# rectifier.net
KiCad netlist of a schematic drawn in EAGLE
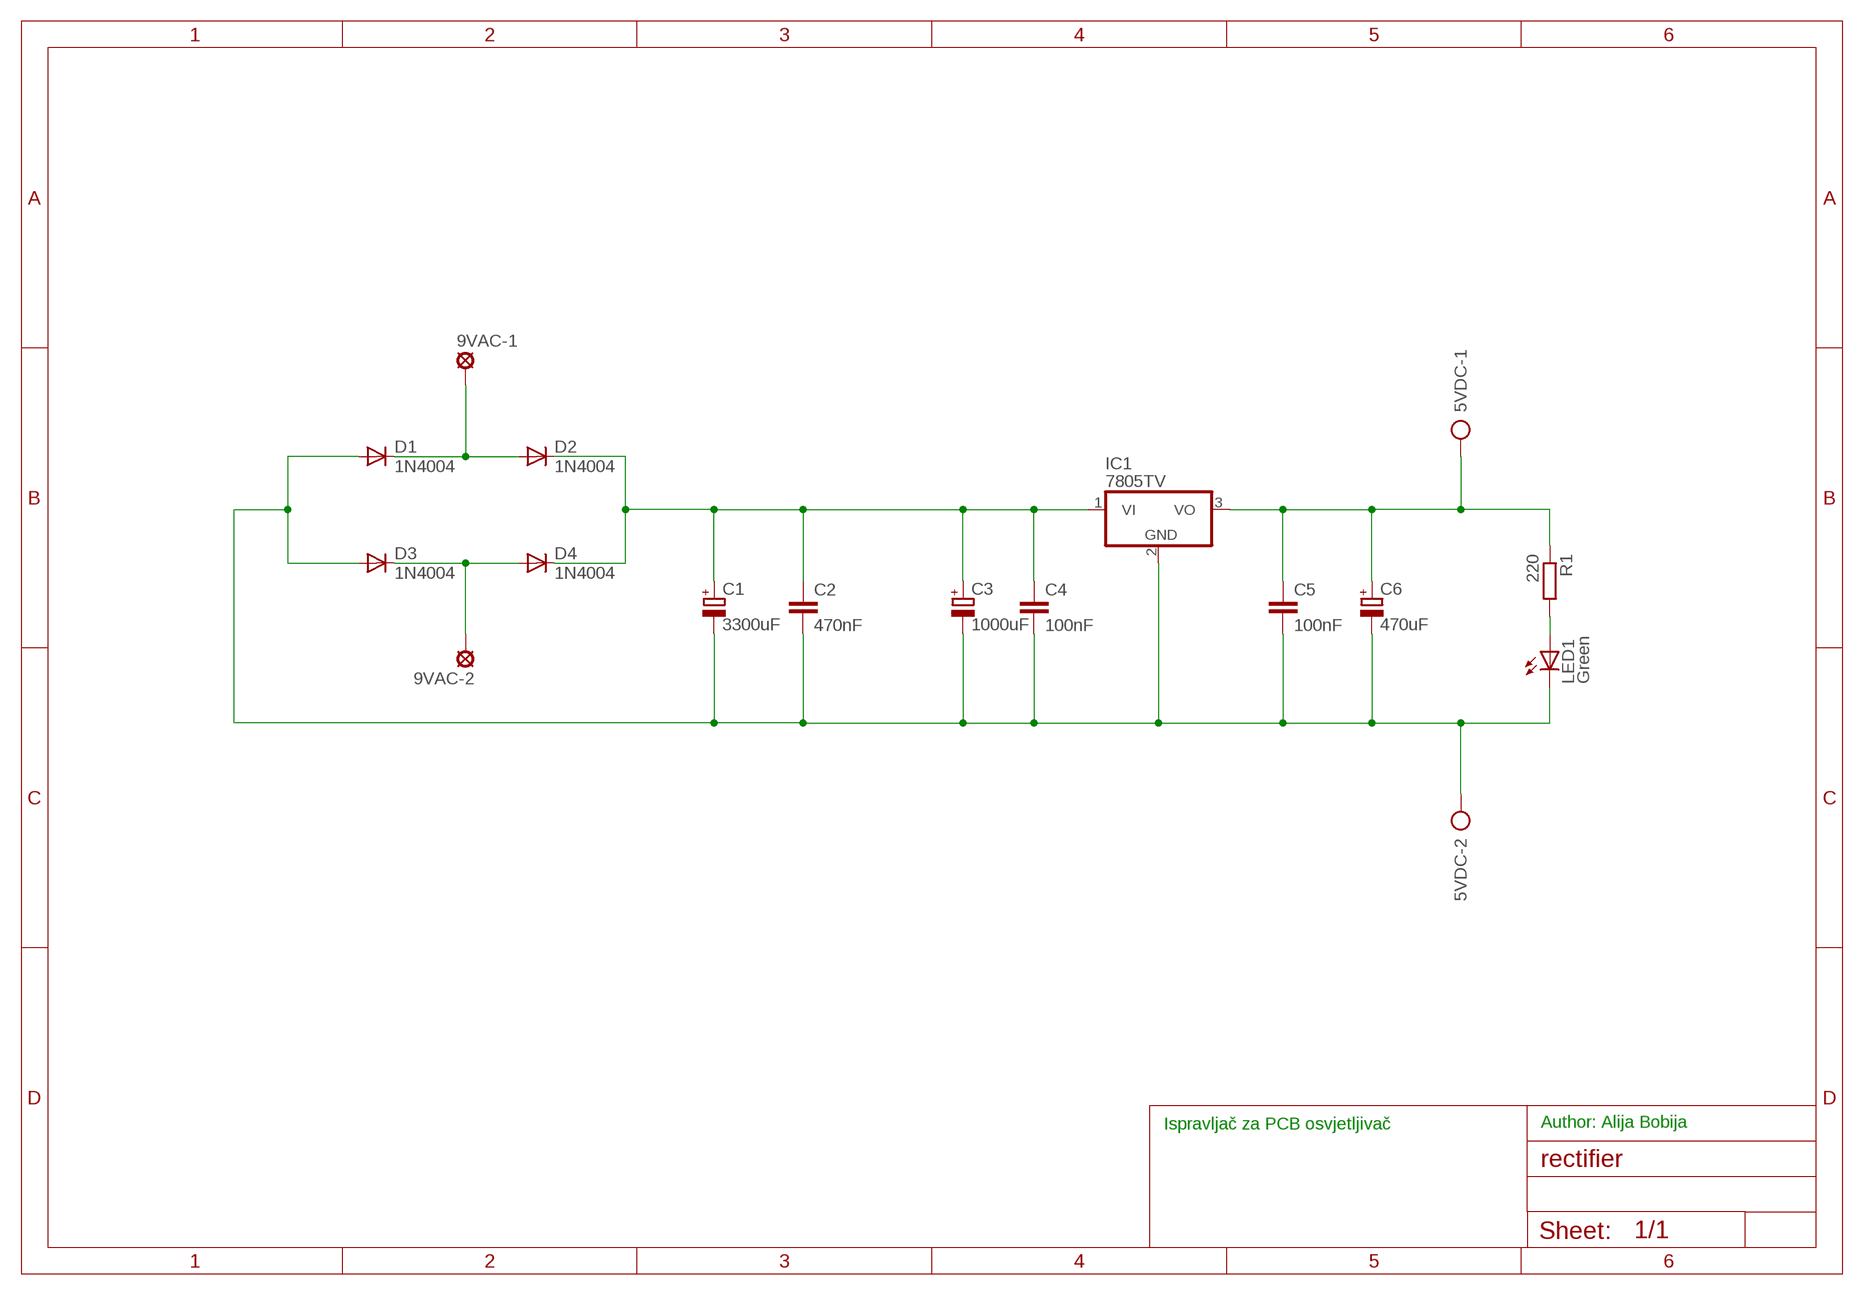
[diagram p0: schematic, sheet 1]

(export (version "E")
  (design (tool "Eeschema 10.0.6"))
  (components
    (comp (ref "5VDC")
      (value "AK500/2")
      (footprint "eagle-import:AK500_2")
      (libsource (lib "eagle-import") (part "AK500/2"))
    )
    (comp (ref "9VAC-1")
      (value "LSP10")
      (footprint "eagle-import:LSP10")
      (libsource (lib "eagle-import") (part "LSP10"))
    )
    (comp (ref "9VAC-2")
      (value "LSP10")
      (footprint "eagle-import:LSP10")
      (libsource (lib "eagle-import") (part "LSP10"))
    )
    (comp (ref "C1")
      (value "3300uF")
      (footprint "eagle-import:E5-13")
      (libsource (lib "eagle-import") (part "resistor_CPOL-EUE5-13"))
    )
    (comp (ref "C2")
      (value "470nF")
      (footprint "eagle-import:C050-024X044")
      (libsource (lib "eagle-import") (part "resistor_C-EU050-024X044"))
    )
    (comp (ref "C3")
      (value "1000uF")
      (footprint "eagle-import:E3,5-10")
      (libsource (lib "eagle-import") (part "CPOL-EUE3.5-10"))
    )
    (comp (ref "C4")
      (value "100nF")
      (footprint "eagle-import:C025-024X044")
      (libsource (lib "eagle-import") (part "C-EU025-024X044"))
    )
    (comp (ref "C5")
      (value "100nF")
      (footprint "eagle-import:C025-024X044")
      (libsource (lib "eagle-import") (part "C-EU025-024X044"))
    )
    (comp (ref "C6")
      (value "470uF")
      (footprint "eagle-import:E3,5-8")
      (libsource (lib "eagle-import") (part "CPOL-EUE3.5-8"))
    )
    (comp (ref "D1")
      (value "1N4004")
      (footprint "eagle-import:DO41-10")
      (libsource (lib "eagle-import") (part "1N4004"))
    )
    (comp (ref "D2")
      (value "1N4004")
      (footprint "eagle-import:DO41-10")
      (libsource (lib "eagle-import") (part "1N4004"))
    )
    (comp (ref "D3")
      (value "1N4004")
      (footprint "eagle-import:DO41-10")
      (libsource (lib "eagle-import") (part "1N4004"))
    )
    (comp (ref "D4")
      (value "1N4004")
      (footprint "eagle-import:DO41-10")
      (libsource (lib "eagle-import") (part "1N4004"))
    )
    (comp (ref "IC1")
      (value "7805TV")
      (footprint "eagle-import:TO220V")
      (libsource (lib "eagle-import") (part "78TV05"))
    )
    (comp (ref "LED1")
      (value "Green")
      (footprint "eagle-import:LED3MM")
      (libsource (lib "eagle-import") (part "LED3MM"))
    )
    (comp (ref "R1")
      (value "220")
      (footprint "eagle-import:M0805")
      (libsource (lib "eagle-import") (part "R-EU_M0805"))
    )
  )
  (nets
    (net (code "1") (name "Net-(5VDCA-KL)") (class "Default")
      (node (ref "5VDC") (pin "1") (pinfunction "KL_1") (pintype "passive"))
      (node (ref "C5") (pin "1") (pinfunction "1_1") (pintype "passive"))
      (node (ref "C6") (pin "+") (pinfunction "+_+") (pintype "passive"))
      (node (ref "IC1") (pin "3") (pinfunction "VO_3") (pintype "passive"))
      (node (ref "R1") (pin "1") (pinfunction "1_1") (pintype "passive"))
    )
    (net (code "2") (name "Net-(5VDCB-KL)") (class "Default")
      (node (ref "5VDC") (pin "2") (pinfunction "KL_2") (pintype "passive"))
      (node (ref "C1") (pin "-") (pinfunction "-_-") (pintype "passive"))
      (node (ref "C2") (pin "2") (pinfunction "2_2") (pintype "passive"))
      (node (ref "C3") (pin "-") (pinfunction "-_-") (pintype "passive"))
      (node (ref "C4") (pin "2") (pinfunction "2_2") (pintype "passive"))
      (node (ref "C5") (pin "2") (pinfunction "2_2") (pintype "passive"))
      (node (ref "C6") (pin "-") (pinfunction "-_-") (pintype "passive"))
      (node (ref "D1") (pin "A") (pinfunction "A_A") (pintype "passive"))
      (node (ref "D3") (pin "A") (pinfunction "A_A") (pintype "passive"))
      (node (ref "IC1") (pin "2") (pinfunction "GND_2") (pintype "passive"))
      (node (ref "LED1") (pin "K") (pinfunction "C_K") (pintype "passive"))
    )
    (net (code "3") (name "Net-(9VAC-1-PadMP)") (class "Default")
      (node (ref "9VAC-1") (pin "MP") (pinfunction "MP_MP") (pintype "passive"))
      (node (ref "D1") (pin "C") (pinfunction "C_C") (pintype "passive"))
      (node (ref "D2") (pin "A") (pinfunction "A_A") (pintype "passive"))
    )
    (net (code "4") (name "Net-(9VAC-2-PadMP)") (class "Default")
      (node (ref "9VAC-2") (pin "MP") (pinfunction "MP_MP") (pintype "passive"))
      (node (ref "D3") (pin "C") (pinfunction "C_C") (pintype "passive"))
      (node (ref "D4") (pin "A") (pinfunction "A_A") (pintype "passive"))
    )
    (net (code "5") (name "Net-(IC1-VI)") (class "Default")
      (node (ref "C1") (pin "+") (pinfunction "+_+") (pintype "passive"))
      (node (ref "C2") (pin "1") (pinfunction "1_1") (pintype "passive"))
      (node (ref "C3") (pin "+") (pinfunction "+_+") (pintype "passive"))
      (node (ref "C4") (pin "1") (pinfunction "1_1") (pintype "passive"))
      (node (ref "D2") (pin "C") (pinfunction "C_C") (pintype "passive"))
      (node (ref "D4") (pin "C") (pinfunction "C_C") (pintype "passive"))
      (node (ref "IC1") (pin "1") (pinfunction "VI_1") (pintype "input"))
    )
    (net (code "6") (name "Net-(LED1-PadA)") (class "Default")
      (node (ref "LED1") (pin "A") (pinfunction "A_A") (pintype "passive"))
      (node (ref "R1") (pin "2") (pinfunction "2_2") (pintype "passive"))
    )
  )
)
